# handpiece.net
KiCad netlist of a schematic drawn in EAGLE
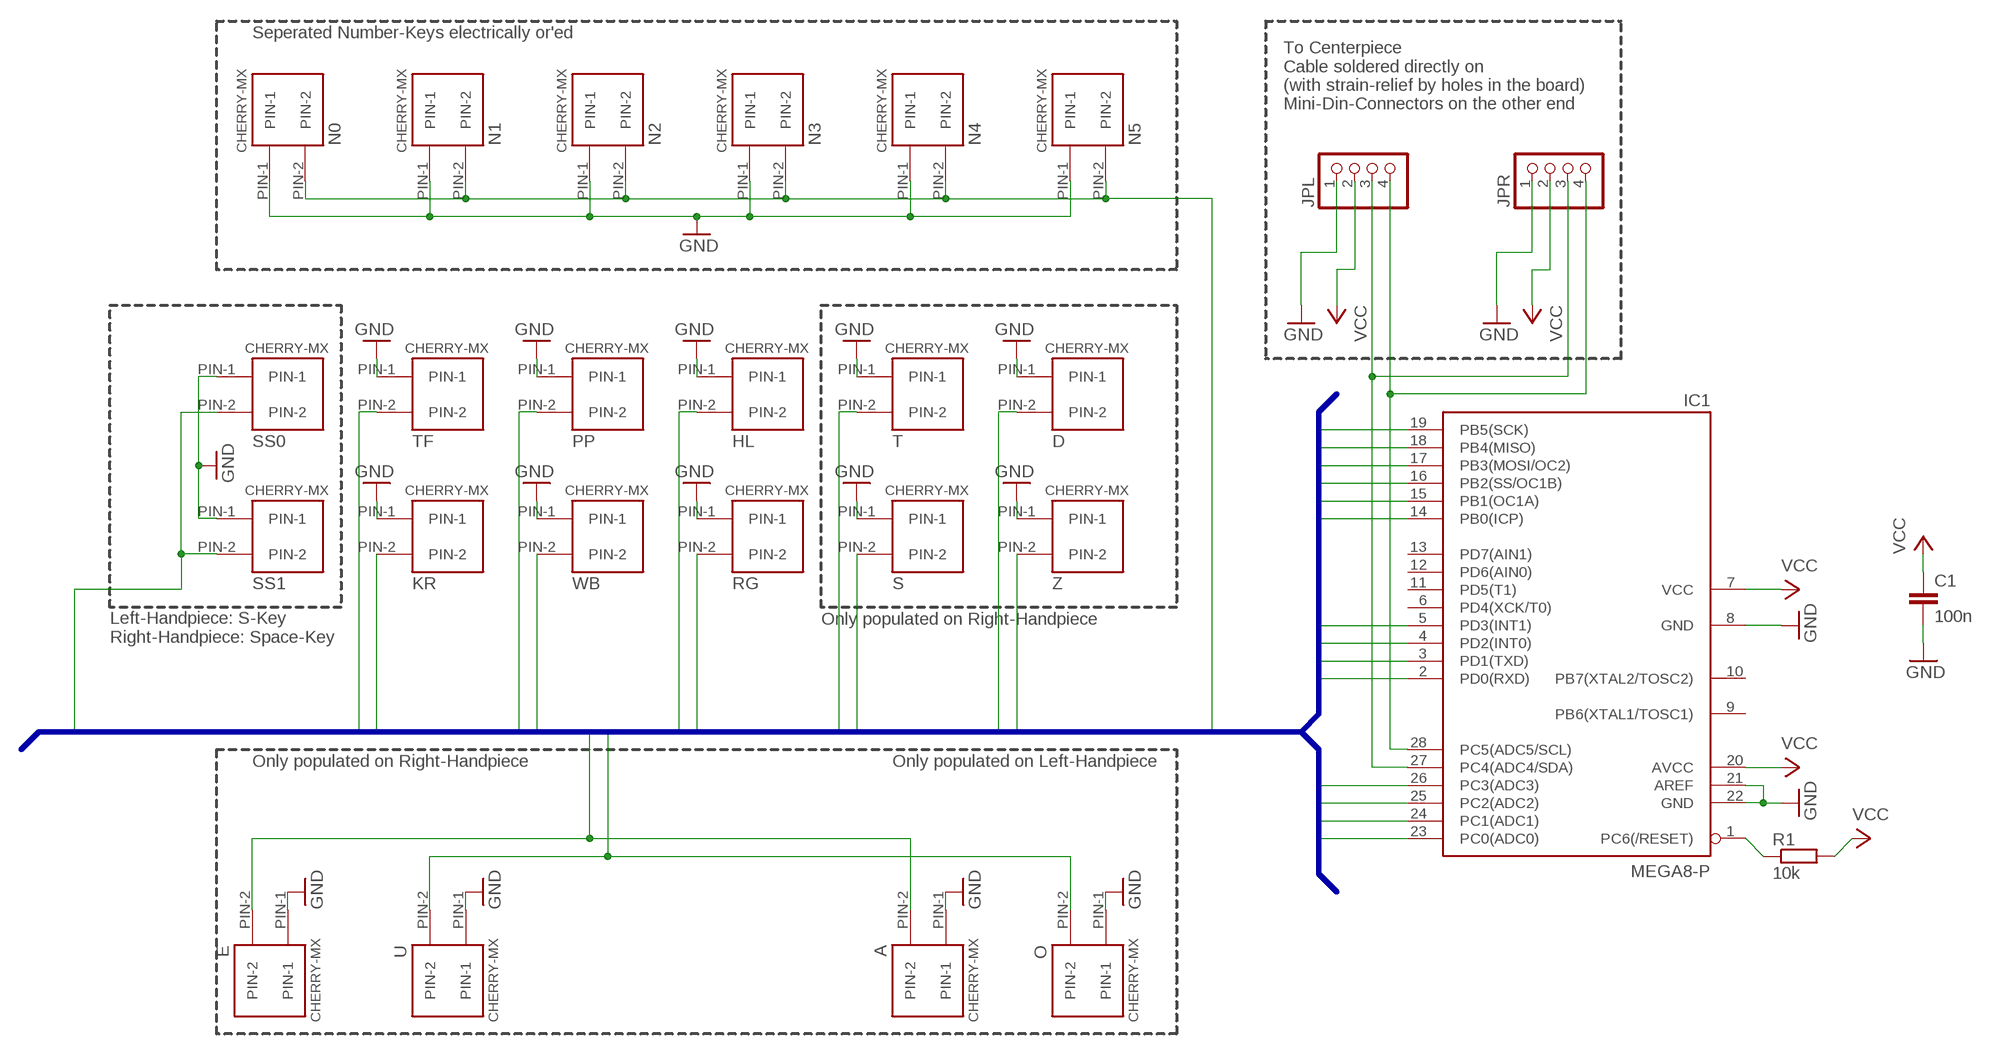
[diagram p0: schematic, sheet 1]

(export (version "E")
  (design (tool "Eeschema 10.0.6"))
  (components
    (comp (ref "A")
      (value "CHERRY-MX-I")
      (footprint "eagle-import:CHERRY-MX-I")
      (libsource (lib "eagle-import") (part "CHERRY-MX-I"))
    )
    (comp (ref "C1")
      (value "100n")
      (footprint "eagle-import:C075-032X103")
      (libsource (lib "eagle-import") (part "C-EU075-032X103"))
    )
    (comp (ref "D")
      (value "CHERRY-MX-I")
      (footprint "eagle-import:CHERRY-MX-I")
      (libsource (lib "eagle-import") (part "CHERRY-MX-I"))
    )
    (comp (ref "E")
      (value "CHERRY-MX-I")
      (footprint "eagle-import:CHERRY-MX-I")
      (libsource (lib "eagle-import") (part "CHERRY-MX-I"))
    )
    (comp (ref "HL")
      (value "CHERRY-MX-I")
      (footprint "eagle-import:CHERRY-MX-I")
      (libsource (lib "eagle-import") (part "CHERRY-MX-I"))
    )
    (comp (ref "IC1")
      (value "MEGA8-P")
      (footprint "eagle-import:DIL28-3")
      (libsource (lib "eagle-import") (part "MEGA8-P"))
    )
    (comp (ref "JPL")
      (value "PINHD-1X4")
      (footprint "eagle-import:1X04")
      (libsource (lib "eagle-import") (part "PINHD-1X4"))
    )
    (comp (ref "JPR")
      (value "PINHD-1X4")
      (footprint "eagle-import:1X04")
      (libsource (lib "eagle-import") (part "PINHD-1X4"))
    )
    (comp (ref "KR")
      (value "CHERRY-MX-I")
      (footprint "eagle-import:CHERRY-MX-I")
      (libsource (lib "eagle-import") (part "CHERRY-MX-I"))
    )
    (comp (ref "N0")
      (value "CHERRY-MX-I")
      (footprint "eagle-import:CHERRY-MX-I")
      (libsource (lib "eagle-import") (part "CHERRY-MX-I"))
    )
    (comp (ref "N1")
      (value "CHERRY-MX-I")
      (footprint "eagle-import:CHERRY-MX-I")
      (libsource (lib "eagle-import") (part "CHERRY-MX-I"))
    )
    (comp (ref "N2")
      (value "CHERRY-MX-I")
      (footprint "eagle-import:CHERRY-MX-I")
      (libsource (lib "eagle-import") (part "CHERRY-MX-I"))
    )
    (comp (ref "N3")
      (value "CHERRY-MX-I")
      (footprint "eagle-import:CHERRY-MX-I")
      (libsource (lib "eagle-import") (part "CHERRY-MX-I"))
    )
    (comp (ref "N4")
      (value "CHERRY-MX-I")
      (footprint "eagle-import:CHERRY-MX-I")
      (libsource (lib "eagle-import") (part "CHERRY-MX-I"))
    )
    (comp (ref "N5")
      (value "CHERRY-MX-I")
      (footprint "eagle-import:CHERRY-MX-I")
      (libsource (lib "eagle-import") (part "CHERRY-MX-I"))
    )
    (comp (ref "O")
      (value "CHERRY-MX-I")
      (footprint "eagle-import:CHERRY-MX-I")
      (libsource (lib "eagle-import") (part "CHERRY-MX-I"))
    )
    (comp (ref "PP")
      (value "CHERRY-MX-I")
      (footprint "eagle-import:CHERRY-MX-I")
      (libsource (lib "eagle-import") (part "CHERRY-MX-I"))
    )
    (comp (ref "R1")
      (value "10k")
      (footprint "eagle-import:0207_7")
      (libsource (lib "eagle-import") (part "R-EU_0207/7"))
    )
    (comp (ref "RG")
      (value "CHERRY-MX-I")
      (footprint "eagle-import:CHERRY-MX-I")
      (libsource (lib "eagle-import") (part "CHERRY-MX-I"))
    )
    (comp (ref "S")
      (value "CHERRY-MX-I")
      (footprint "eagle-import:CHERRY-MX-I")
      (libsource (lib "eagle-import") (part "CHERRY-MX-I"))
    )
    (comp (ref "SS0")
      (value "CHERRY-MX-I")
      (footprint "eagle-import:CHERRY-MX-I")
      (libsource (lib "eagle-import") (part "CHERRY-MX-I"))
    )
    (comp (ref "SS1")
      (value "CHERRY-MX-I")
      (footprint "eagle-import:CHERRY-MX-I")
      (libsource (lib "eagle-import") (part "CHERRY-MX-I"))
    )
    (comp (ref "T")
      (value "CHERRY-MX-I")
      (footprint "eagle-import:CHERRY-MX-I")
      (libsource (lib "eagle-import") (part "CHERRY-MX-I"))
    )
    (comp (ref "TF")
      (value "CHERRY-MX-I")
      (footprint "eagle-import:CHERRY-MX-I")
      (libsource (lib "eagle-import") (part "CHERRY-MX-I"))
    )
    (comp (ref "U")
      (value "CHERRY-MX-I")
      (footprint "eagle-import:CHERRY-MX-I")
      (libsource (lib "eagle-import") (part "CHERRY-MX-I"))
    )
    (comp (ref "WB")
      (value "CHERRY-MX-I")
      (footprint "eagle-import:CHERRY-MX-I")
      (libsource (lib "eagle-import") (part "CHERRY-MX-I"))
    )
    (comp (ref "Z")
      (value "CHERRY-MX-I")
      (footprint "eagle-import:CHERRY-MX-I")
      (libsource (lib "eagle-import") (part "CHERRY-MX-I"))
    )
  )
  (nets
    (net (code "1") (name "/D") (class "Default")
      (node (ref "D") (pin "PIN-2") (pinfunction "PIN-2_PIN-2") (pintype "bidirectional"))
      (node (ref "IC1") (pin "15") (pinfunction "PB1(OC1A)_15") (pintype "bidirectional"))
    )
    (net (code "2") (name "/EA") (class "Default")
      (node (ref "A") (pin "PIN-2") (pinfunction "PIN-2_PIN-2") (pintype "bidirectional"))
      (node (ref "E") (pin "PIN-2") (pinfunction "PIN-2_PIN-2") (pintype "bidirectional"))
      (node (ref "IC1") (pin "4") (pinfunction "PD2(INT0)_4") (pintype "bidirectional"))
    )
    (net (code "3") (name "/HL") (class "Default")
      (node (ref "HL") (pin "PIN-2") (pinfunction "PIN-2_PIN-2") (pintype "bidirectional"))
      (node (ref "IC1") (pin "23") (pinfunction "PC0(ADC0)_23") (pintype "bidirectional"))
    )
    (net (code "4") (name "/KR") (class "Default")
      (node (ref "IC1") (pin "2") (pinfunction "PD0(RXD)_2") (pintype "bidirectional"))
      (node (ref "KR") (pin "PIN-2") (pinfunction "PIN-2_PIN-2") (pintype "bidirectional"))
    )
    (net (code "5") (name "/N") (class "Default")
      (node (ref "IC1") (pin "14") (pinfunction "PB0(ICP)_14") (pintype "bidirectional"))
      (node (ref "N0") (pin "PIN-2") (pinfunction "PIN-2_PIN-2") (pintype "bidirectional"))
      (node (ref "N1") (pin "PIN-2") (pinfunction "PIN-2_PIN-2") (pintype "bidirectional"))
      (node (ref "N2") (pin "PIN-2") (pinfunction "PIN-2_PIN-2") (pintype "bidirectional"))
      (node (ref "N3") (pin "PIN-2") (pinfunction "PIN-2_PIN-2") (pintype "bidirectional"))
      (node (ref "N4") (pin "PIN-2") (pinfunction "PIN-2_PIN-2") (pintype "bidirectional"))
      (node (ref "N5") (pin "PIN-2") (pinfunction "PIN-2_PIN-2") (pintype "bidirectional"))
    )
    (net (code "6") (name "/OU") (class "Default")
      (node (ref "IC1") (pin "5") (pinfunction "PD3(INT1)_5") (pintype "bidirectional"))
      (node (ref "O") (pin "PIN-2") (pinfunction "PIN-2_PIN-2") (pintype "bidirectional"))
      (node (ref "U") (pin "PIN-2") (pinfunction "PIN-2_PIN-2") (pintype "bidirectional"))
    )
    (net (code "7") (name "/PP") (class "Default")
      (node (ref "IC1") (pin "24") (pinfunction "PC1(ADC1)_24") (pintype "bidirectional"))
      (node (ref "PP") (pin "PIN-2") (pinfunction "PIN-2_PIN-2") (pintype "bidirectional"))
    )
    (net (code "8") (name "/RG") (class "Default")
      (node (ref "IC1") (pin "19") (pinfunction "PB5(SCK)_19") (pintype "bidirectional"))
      (node (ref "RG") (pin "PIN-2") (pinfunction "PIN-2_PIN-2") (pintype "bidirectional"))
    )
    (net (code "9") (name "/S") (class "Default")
      (node (ref "IC1") (pin "17") (pinfunction "PB3(MOSI/OC2)_17") (pintype "bidirectional"))
      (node (ref "S") (pin "PIN-2") (pinfunction "PIN-2_PIN-2") (pintype "bidirectional"))
    )
    (net (code "10") (name "/SS") (class "Default")
      (node (ref "IC1") (pin "3") (pinfunction "PD1(TXD)_3") (pintype "bidirectional"))
      (node (ref "SS0") (pin "PIN-2") (pinfunction "PIN-2_PIN-2") (pintype "bidirectional"))
      (node (ref "SS1") (pin "PIN-2") (pinfunction "PIN-2_PIN-2") (pintype "bidirectional"))
    )
    (net (code "11") (name "/T") (class "Default")
      (node (ref "IC1") (pin "18") (pinfunction "PB4(MISO)_18") (pintype "bidirectional"))
      (node (ref "T") (pin "PIN-2") (pinfunction "PIN-2_PIN-2") (pintype "bidirectional"))
    )
    (net (code "12") (name "/TF") (class "Default")
      (node (ref "IC1") (pin "26") (pinfunction "PC3(ADC3)_26") (pintype "bidirectional"))
      (node (ref "TF") (pin "PIN-2") (pinfunction "PIN-2_PIN-2") (pintype "bidirectional"))
    )
    (net (code "13") (name "/WB") (class "Default")
      (node (ref "IC1") (pin "25") (pinfunction "PC2(ADC2)_25") (pintype "bidirectional"))
      (node (ref "WB") (pin "PIN-2") (pinfunction "PIN-2_PIN-2") (pintype "bidirectional"))
    )
    (net (code "14") (name "/Z") (class "Default")
      (node (ref "IC1") (pin "16") (pinfunction "PB2(SS/OC1B)_16") (pintype "bidirectional"))
      (node (ref "Z") (pin "PIN-2") (pinfunction "PIN-2_PIN-2") (pintype "bidirectional"))
    )
    (net (code "15") (name "GND") (class "Default")
      (node (ref "A") (pin "PIN-1") (pinfunction "PIN-1_PIN-1") (pintype "bidirectional"))
      (node (ref "C1") (pin "2") (pinfunction "2_2") (pintype "passive"))
      (node (ref "D") (pin "PIN-1") (pinfunction "PIN-1_PIN-1") (pintype "bidirectional"))
      (node (ref "E") (pin "PIN-1") (pinfunction "PIN-1_PIN-1") (pintype "bidirectional"))
      (node (ref "HL") (pin "PIN-1") (pinfunction "PIN-1_PIN-1") (pintype "bidirectional"))
      (node (ref "IC1") (pin "21") (pinfunction "AREF_21") (pintype "passive"))
      (node (ref "IC1") (pin "22") (pinfunction "GND_22") (pintype "power_in"))
      (node (ref "IC1") (pin "8") (pinfunction "GND_8") (pintype "power_in"))
      (node (ref "JPL") (pin "1") (pinfunction "1_1") (pintype "passive"))
      (node (ref "JPR") (pin "1") (pinfunction "1_1") (pintype "passive"))
      (node (ref "KR") (pin "PIN-1") (pinfunction "PIN-1_PIN-1") (pintype "bidirectional"))
      (node (ref "N0") (pin "PIN-1") (pinfunction "PIN-1_PIN-1") (pintype "bidirectional"))
      (node (ref "N1") (pin "PIN-1") (pinfunction "PIN-1_PIN-1") (pintype "bidirectional"))
      (node (ref "N2") (pin "PIN-1") (pinfunction "PIN-1_PIN-1") (pintype "bidirectional"))
      (node (ref "N3") (pin "PIN-1") (pinfunction "PIN-1_PIN-1") (pintype "bidirectional"))
      (node (ref "N4") (pin "PIN-1") (pinfunction "PIN-1_PIN-1") (pintype "bidirectional"))
      (node (ref "N5") (pin "PIN-1") (pinfunction "PIN-1_PIN-1") (pintype "bidirectional"))
      (node (ref "O") (pin "PIN-1") (pinfunction "PIN-1_PIN-1") (pintype "bidirectional"))
      (node (ref "PP") (pin "PIN-1") (pinfunction "PIN-1_PIN-1") (pintype "bidirectional"))
      (node (ref "RG") (pin "PIN-1") (pinfunction "PIN-1_PIN-1") (pintype "bidirectional"))
      (node (ref "S") (pin "PIN-1") (pinfunction "PIN-1_PIN-1") (pintype "bidirectional"))
      (node (ref "SS0") (pin "PIN-1") (pinfunction "PIN-1_PIN-1") (pintype "bidirectional"))
      (node (ref "SS1") (pin "PIN-1") (pinfunction "PIN-1_PIN-1") (pintype "bidirectional"))
      (node (ref "T") (pin "PIN-1") (pinfunction "PIN-1_PIN-1") (pintype "bidirectional"))
      (node (ref "TF") (pin "PIN-1") (pinfunction "PIN-1_PIN-1") (pintype "bidirectional"))
      (node (ref "U") (pin "PIN-1") (pinfunction "PIN-1_PIN-1") (pintype "bidirectional"))
      (node (ref "WB") (pin "PIN-1") (pinfunction "PIN-1_PIN-1") (pintype "bidirectional"))
      (node (ref "Z") (pin "PIN-1") (pinfunction "PIN-1_PIN-1") (pintype "bidirectional"))
    )
    (net (code "16") (name "Net-(IC1-PC4(ADC4{slash}SDA))") (class "Default")
      (node (ref "IC1") (pin "27") (pinfunction "PC4(ADC4/SDA)_27") (pintype "bidirectional"))
      (node (ref "JPL") (pin "3") (pinfunction "3_3") (pintype "passive"))
      (node (ref "JPR") (pin "3") (pinfunction "3_3") (pintype "passive"))
    )
    (net (code "17") (name "Net-(IC1-PC5(ADC5{slash}SCL))") (class "Default")
      (node (ref "IC1") (pin "28") (pinfunction "PC5(ADC5/SCL)_28") (pintype "bidirectional"))
      (node (ref "JPL") (pin "4") (pinfunction "4_4") (pintype "passive"))
      (node (ref "JPR") (pin "4") (pinfunction "4_4") (pintype "passive"))
    )
    (net (code "18") (name "Net-(IC1-PC6({slash}RESET))") (class "Default")
      (node (ref "IC1") (pin "1") (pinfunction "PC6(/RESET)_1") (pintype "bidirectional"))
      (node (ref "R1") (pin "1") (pinfunction "1_1") (pintype "passive"))
    )
    (net (code "19") (name "VCC") (class "Default")
      (node (ref "C1") (pin "1") (pinfunction "1_1") (pintype "passive"))
      (node (ref "IC1") (pin "20") (pinfunction "AVCC_20") (pintype "power_in"))
      (node (ref "IC1") (pin "7") (pinfunction "VCC_7") (pintype "power_in"))
      (node (ref "JPL") (pin "2") (pinfunction "2_2") (pintype "passive"))
      (node (ref "JPR") (pin "2") (pinfunction "2_2") (pintype "passive"))
      (node (ref "R1") (pin "2") (pinfunction "2_2") (pintype "passive"))
    )
    (net (code "20") (name "unconnected-(IC1-PB6(XTAL1{slash}TOSC1)-Pad9)") (class "Default")
      (node (ref "IC1") (pin "9") (pinfunction "PB6(XTAL1/TOSC1)_9") (pintype "bidirectional"))
    )
    (net (code "21") (name "unconnected-(IC1-PB7(XTAL2{slash}TOSC2)-Pad10)") (class "Default")
      (node (ref "IC1") (pin "10") (pinfunction "PB7(XTAL2/TOSC2)_10") (pintype "bidirectional"))
    )
    (net (code "22") (name "unconnected-(IC1-PD4(XCK{slash}T0)-Pad6)") (class "Default")
      (node (ref "IC1") (pin "6") (pinfunction "PD4(XCK/T0)_6") (pintype "bidirectional"))
    )
    (net (code "23") (name "unconnected-(IC1-PD5(T1)-Pad11)") (class "Default")
      (node (ref "IC1") (pin "11") (pinfunction "PD5(T1)_11") (pintype "bidirectional"))
    )
    (net (code "24") (name "unconnected-(IC1-PD6(AIN0)-Pad12)") (class "Default")
      (node (ref "IC1") (pin "12") (pinfunction "PD6(AIN0)_12") (pintype "bidirectional"))
    )
    (net (code "25") (name "unconnected-(IC1-PD7(AIN1)-Pad13)") (class "Default")
      (node (ref "IC1") (pin "13") (pinfunction "PD7(AIN1)_13") (pintype "bidirectional"))
    )
  )
)
